# MercurialSDR_FTDI.net
KiCad netlist of a schematic drawn in Altium Designer
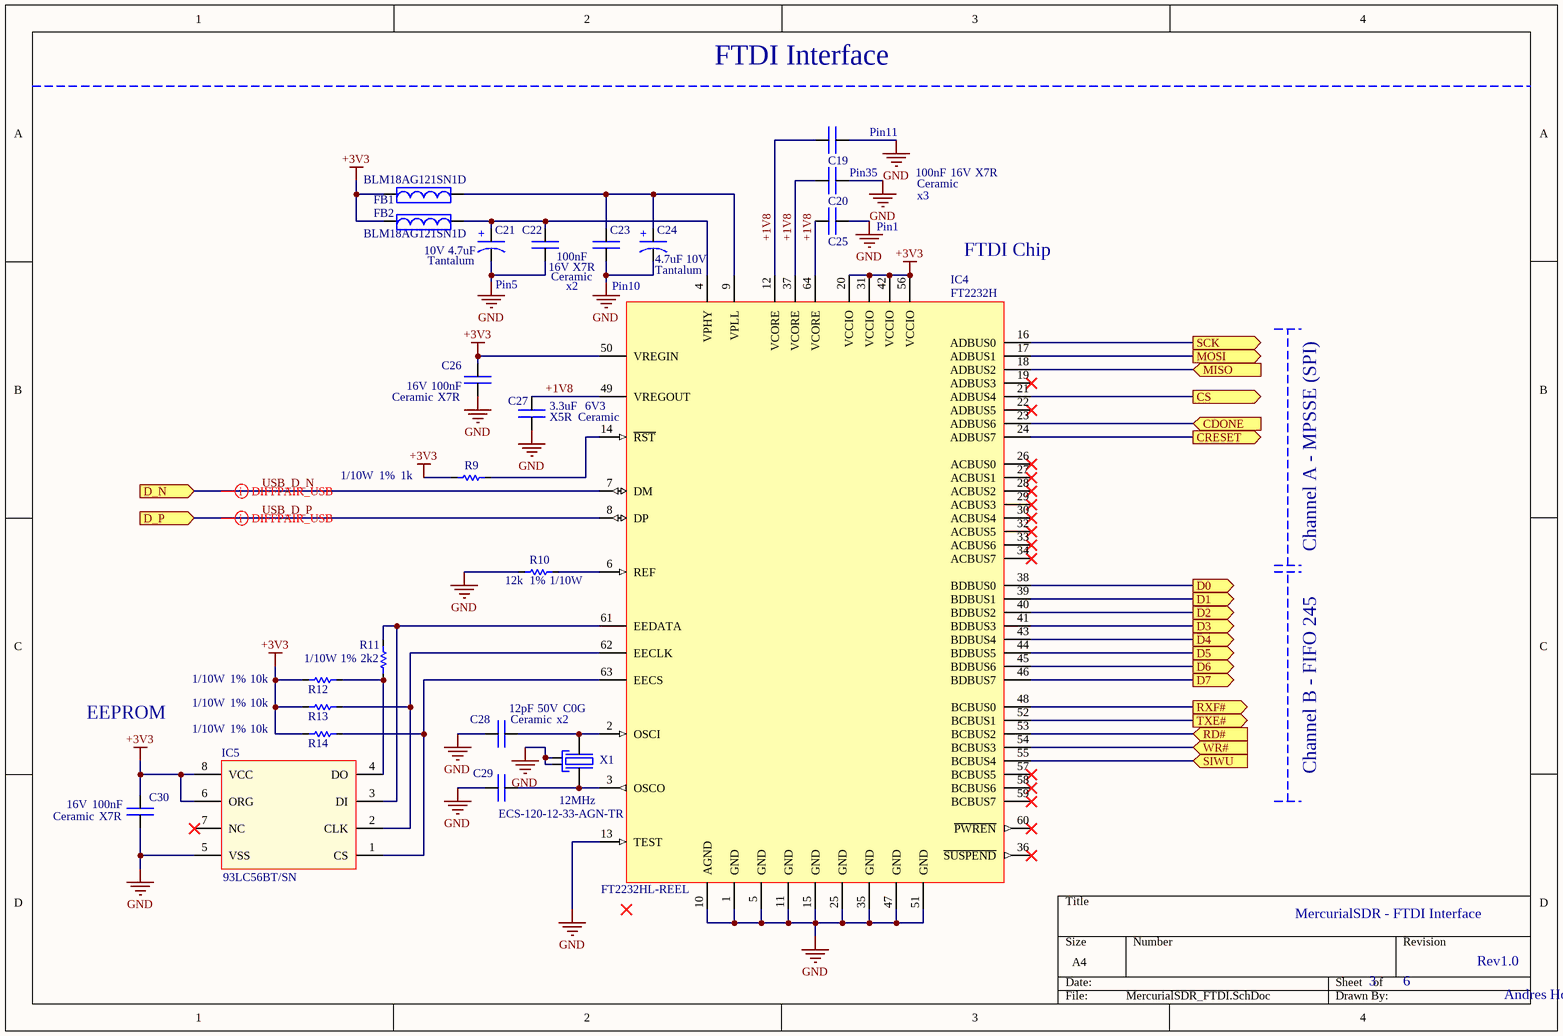
[diagram p0: MercurialSDR_FTDI.SchDoc]

(export (version "E")
  (design (tool "Eeschema 10.0.6"))
  (components
    (comp (ref "C19")
      (value "100nF")
      (footprint "CAP_0603")
      (description "Capacitor no polarizado")
      (fields
        (field (name "TEMP COEF") "X7R")
        (field (name "PART NUMBER") "CL10B104KO8NNNC")
        (field (name "VR") "16V")
        (field (name "MATERIAL") "Ceramic")
        (field (name "Comment") "Capacitor")
      )
      (libsource (lib "MercurialSDR") (part "Cap"))
    )
    (comp (ref "C20")
      (value "Capacitor")
      (footprint "CAP_0603")
      (description "Capacitor no polarizado")
      (fields (field (name "PART NUMBER") "CL10B104KO8NNNC"))
      (libsource (lib "MercurialSDR") (part "Cap"))
    )
    (comp (ref "C21")
      (value "4.7uF")
      (footprint "CAP_TANT_1206")
      (description "Capacitor polarizado")
      (fields
        (field (name "PART NUMBER") "TAJA475K010RNJ")
        (field (name "VR") "10V")
        (field (name "MATERIAL") "Tantalum")
        (field (name "Comment") "Capacitor Polarizado")
      )
      (libsource (lib "MercurialSDR") (part "Cap Pol"))
    )
    (comp (ref "C22")
      (value "100nF")
      (footprint "CAP_0603")
      (description "Capacitor no polarizado")
      (fields
        (field (name "TEMP COEF") "X7R")
        (field (name "PART NUMBER") "CL10B104KO8NNNC")
        (field (name "VR") "16V")
        (field (name "MATERIAL") "Ceramic")
        (field (name "Comment") "Capacitor")
      )
      (libsource (lib "MercurialSDR") (part "Cap"))
    )
    (comp (ref "C23")
      (value "Capacitor")
      (footprint "CAP_0603")
      (description "Capacitor no polarizado")
      (fields (field (name "PART NUMBER") "CL10B104KO8NNNC"))
      (libsource (lib "MercurialSDR") (part "Cap"))
    )
    (comp (ref "C24")
      (value "4.7uF")
      (footprint "CAP_TANT_1206")
      (description "Capacitor polarizado")
      (fields
        (field (name "PART NUMBER") "TAJA475K010RNJ")
        (field (name "VR") "10V")
        (field (name "MATERIAL") "Tantalum")
        (field (name "Comment") "Capacitor Polarizado")
      )
      (libsource (lib "MercurialSDR") (part "Cap Pol"))
    )
    (comp (ref "C25")
      (value "Capacitor")
      (footprint "CAP_0603")
      (description "Capacitor no polarizado")
      (fields (field (name "PART NUMBER") "CL10B104KO8NNNC"))
      (libsource (lib "MercurialSDR") (part "Cap"))
    )
    (comp (ref "C26")
      (value "100nF")
      (footprint "CAP_0603")
      (description "Capacitor no polarizado")
      (fields
        (field (name "TEMP COEF") "X7R")
        (field (name "PART NUMBER") "CL10B104KO8NNNC")
        (field (name "VR") "16V")
        (field (name "MATERIAL") "Ceramic")
        (field (name "Comment") "Capacitor")
      )
      (libsource (lib "MercurialSDR") (part "Cap"))
    )
    (comp (ref "C27")
      (value "3.3uF")
      (footprint "CAP_0603")
      (description "Capacitor no polarizado")
      (fields
        (field (name "TEMP COEF") "X5R")
        (field (name "PART NUMBER") "C0603C335M9PACTU")
        (field (name "VR") "6V3")
        (field (name "MATERIAL") "Ceramic")
        (field (name "Comment") "Capacitor")
      )
      (libsource (lib "MercurialSDR") (part "Cap"))
    )
    (comp (ref "C28")
      (value "12pF")
      (footprint "CAP_0603")
      (description "Capacitor no polarizado")
      (fields
        (field (name "TEMP COEF") "C0G")
        (field (name "PART NUMBER") "CL10C120JB8NNNC")
        (field (name "VR") "50V")
        (field (name "MATERIAL") "Ceramic")
        (field (name "Comment") "Capacitor")
      )
      (libsource (lib "MercurialSDR") (part "Cap"))
    )
    (comp (ref "C29")
      (value "Capacitor")
      (footprint "CAP_0603")
      (description "Capacitor no polarizado")
      (fields (field (name "PART NUMBER") "CL10C120JB8NNNC"))
      (libsource (lib "MercurialSDR") (part "Cap"))
    )
    (comp (ref "C30")
      (value "100nF")
      (footprint "CAP_0603")
      (description "Capacitor no polarizado")
      (fields
        (field (name "TEMP COEF") "X7R")
        (field (name "PART NUMBER") "CL10B104KO8NNNC")
        (field (name "VR") "16V")
        (field (name "MATERIAL") "Ceramic")
        (field (name "Comment") "Capacitor")
      )
      (libsource (lib "MercurialSDR") (part "Cap"))
    )
    (comp (ref "FB1")
      (value "Ferrite Bead")
      (footprint "FERRITE_BEAD_0603")
      (fields (field (name "PART NUMBER") "BLM18AG121SN1D"))
      (libsource (lib "MercurialSDR") (part "Ferrite Bead"))
    )
    (comp (ref "FB2")
      (value "Ferrite Bead")
      (footprint "FERRITE_BEAD_0603")
      (fields (field (name "PART NUMBER") "BLM18AG121SN1D"))
      (libsource (lib "MercurialSDR") (part "Ferrite Bead"))
    )
    (comp (ref "IC4")
      (value "FT2232H")
      (footprint "LQFP_64")
      (description "USB bridge")
      (fields (field (name "PART NUMBER") "FT2232HL-REEL"))
      (libsource (lib "MercurialSDR") (part "FT2232H"))
    )
    (comp (ref "IC5")
      (value "93LC56BT")
      (footprint "SOIC-8")
      (description "EEPROM SPI 2kb (128x16)")
      (fields (field (name "PART NUMBER") "93LC56BT/SN"))
      (libsource (lib "MercurialSDR") (part "93LC56BT/SN"))
    )
    (comp (ref "R9")
      (value "1k")
      (footprint "RES_0603")
      (description "Resistor")
      (fields
        (field (name "POWER") "1/10W")
        (field (name "PART NUMBER") "CR0603-FX-1001ELF")
        (field (name "TOLERANCE") "1%")
        (field (name "Comment") "Resistor SMD")
      )
      (libsource (lib "MercurialSDR") (part "Res"))
    )
    (comp (ref "R10")
      (value "12k")
      (footprint "RES_0603")
      (description "Resistor")
      (fields
        (field (name "POWER") "1/10W")
        (field (name "PART NUMBER") "CR0603-FX-1202ELF")
        (field (name "TOLERANCE") "1%")
        (field (name "Comment") "Resistor SMD")
      )
      (libsource (lib "MercurialSDR") (part "Res"))
    )
    (comp (ref "R11")
      (value "2k2")
      (footprint "RES_0603")
      (description "Resistor")
      (fields
        (field (name "POWER") "1/10W")
        (field (name "PART NUMBER") "CR0603-FX-2201ELF")
        (field (name "TOLERANCE") "1%")
        (field (name "Comment") "Resistor SMD")
      )
      (libsource (lib "MercurialSDR") (part "Res"))
    )
    (comp (ref "R12")
      (value "10k")
      (footprint "RES_0603")
      (description "Resistor")
      (fields
        (field (name "POWER") "1/10W")
        (field (name "PART NUMBER") "CR0603-FX-1002EAS")
        (field (name "TOLERANCE") "1%")
        (field (name "Comment") "Resistor SMD")
      )
      (libsource (lib "MercurialSDR") (part "Res"))
    )
    (comp (ref "R13")
      (value "10k")
      (footprint "RES_0603")
      (description "Resistor")
      (fields
        (field (name "POWER") "1/10W")
        (field (name "PART NUMBER") "CR0603-FX-1002EAS")
        (field (name "TOLERANCE") "1%")
        (field (name "Comment") "Resistor SMD")
      )
      (libsource (lib "MercurialSDR") (part "Res"))
    )
    (comp (ref "R14")
      (value "10k")
      (footprint "RES_0603")
      (description "Resistor")
      (fields
        (field (name "POWER") "1/10W")
        (field (name "PART NUMBER") "CR0603-FX-1002EAS")
        (field (name "TOLERANCE") "1%")
        (field (name "Comment") "Resistor SMD")
      )
      (libsource (lib "MercurialSDR") (part "Res"))
    )
    (comp (ref "X1")
      (value "XTAL_4term")
      (footprint "XTAL_3.2x2.5")
      (description "Oscilador a Cristal")
      (fields (field (name "PART NUMBER") "ECS-120-12-33-AGN-TR") (field (name "FRQUENCY") "12MHz"))
      (libsource (lib "MercurialSDR") (part "XTAL_4term"))
    )
  )
  (nets
    (net (code "1") (name "+3V3") (class "Default")
      (node (ref "C26") (pin "1") (pinfunction "1_1") (pintype "passive"))
      (node (ref "C30") (pin "1") (pinfunction "1_1") (pintype "passive"))
      (node (ref "FB1") (pin "1") (pinfunction "1_1") (pintype "passive"))
      (node (ref "FB2") (pin "1") (pinfunction "1_1") (pintype "passive"))
      (node (ref "IC4") (pin "20") (pinfunction "VCCIO_20") (pintype "power_in"))
      (node (ref "IC4") (pin "31") (pinfunction "VCCIO_31") (pintype "power_in"))
      (node (ref "IC4") (pin "42") (pinfunction "VCCIO_42") (pintype "power_in"))
      (node (ref "IC4") (pin "50") (pinfunction "VREGIN_50") (pintype "power_in"))
      (node (ref "IC4") (pin "56") (pinfunction "VCCIO_56") (pintype "power_in"))
      (node (ref "IC5") (pin "6") (pinfunction "ORG_6") (pintype "passive"))
      (node (ref "IC5") (pin "8") (pinfunction "VCC_8") (pintype "passive"))
      (node (ref "R12") (pin "2") (pinfunction "2_2") (pintype "passive"))
      (node (ref "R13") (pin "1") (pinfunction "1_1") (pintype "passive"))
      (node (ref "R14") (pin "1") (pinfunction "1_1") (pintype "passive"))
      (node (ref "R9") (pin "2") (pinfunction "2_2") (pintype "passive"))
    )
    (net (code "2") (name "/+1V8") (class "Default")
      (node (ref "C19") (pin "1") (pinfunction "1_1") (pintype "passive"))
      (node (ref "C20") (pin "1") (pinfunction "1_1") (pintype "passive"))
      (node (ref "C25") (pin "1") (pinfunction "1_1") (pintype "passive"))
      (node (ref "C27") (pin "1") (pinfunction "1_1") (pintype "passive"))
      (node (ref "IC4") (pin "12") (pinfunction "VCORE_12") (pintype "power_in"))
      (node (ref "IC4") (pin "37") (pinfunction "VCORE_37") (pintype "power_in"))
      (node (ref "IC4") (pin "49") (pinfunction "VREGOUT_49") (pintype "power_in"))
      (node (ref "IC4") (pin "64") (pinfunction "VCORE_64") (pintype "power_in"))
    )
    (net (code "3") (name "/CDONE") (class "Default")
      (node (ref "IC4") (pin "23") (pinfunction "ADBUS6_23") (pintype "passive"))
    )
    (net (code "4") (name "/CRESET") (class "Default")
      (node (ref "IC4") (pin "24") (pinfunction "ADBUS7_24") (pintype "passive"))
    )
    (net (code "5") (name "/CS") (class "Default")
      (node (ref "IC4") (pin "21") (pinfunction "ADBUS4_21") (pintype "passive"))
    )
    (net (code "6") (name "/D0") (class "Default")
      (node (ref "IC4") (pin "38") (pinfunction "BDBUS0_38") (pintype "passive"))
    )
    (net (code "7") (name "/D1") (class "Default")
      (node (ref "IC4") (pin "39") (pinfunction "BDBUS1_39") (pintype "passive"))
    )
    (net (code "8") (name "/D2") (class "Default")
      (node (ref "IC4") (pin "40") (pinfunction "BDBUS2_40") (pintype "passive"))
    )
    (net (code "9") (name "/D3") (class "Default")
      (node (ref "IC4") (pin "41") (pinfunction "BDBUS3_41") (pintype "passive"))
    )
    (net (code "10") (name "/D4") (class "Default")
      (node (ref "IC4") (pin "43") (pinfunction "BDBUS4_43") (pintype "passive"))
    )
    (net (code "11") (name "/D5") (class "Default")
      (node (ref "IC4") (pin "44") (pinfunction "BDBUS5_44") (pintype "passive"))
    )
    (net (code "12") (name "/D6") (class "Default")
      (node (ref "IC4") (pin "45") (pinfunction "BDBUS6_45") (pintype "passive"))
    )
    (net (code "13") (name "/D7") (class "Default")
      (node (ref "IC4") (pin "46") (pinfunction "BDBUS7_46") (pintype "passive"))
    )
    (net (code "14") (name "/MISO") (class "Default")
      (node (ref "IC4") (pin "18") (pinfunction "ADBUS2_18") (pintype "passive"))
    )
    (net (code "15") (name "/MOSI") (class "Default")
      (node (ref "IC4") (pin "17") (pinfunction "ADBUS1_17") (pintype "passive"))
    )
    (net (code "16") (name "/RD#") (class "Default")
      (node (ref "IC4") (pin "53") (pinfunction "BCBUS2_53") (pintype "passive"))
    )
    (net (code "17") (name "/RXF#") (class "Default")
      (node (ref "IC4") (pin "48") (pinfunction "BCBUS0_48") (pintype "passive"))
    )
    (net (code "18") (name "/SCK") (class "Default")
      (node (ref "IC4") (pin "16") (pinfunction "ADBUS0_16") (pintype "passive"))
    )
    (net (code "19") (name "/SIWU") (class "Default")
      (node (ref "IC4") (pin "55") (pinfunction "BCBUS4_55") (pintype "passive"))
    )
    (net (code "20") (name "/TXE#") (class "Default")
      (node (ref "IC4") (pin "52") (pinfunction "BCBUS1_52") (pintype "passive"))
    )
    (net (code "21") (name "/USB_D_N") (class "Default")
      (node (ref "IC4") (pin "7") (pinfunction "DM_7") (pintype "bidirectional"))
    )
    (net (code "22") (name "/USB_D_P") (class "Default")
      (node (ref "IC4") (pin "8") (pinfunction "DP_8") (pintype "bidirectional"))
    )
    (net (code "23") (name "/WR#") (class "Default")
      (node (ref "IC4") (pin "54") (pinfunction "BCBUS3_54") (pintype "passive"))
    )
    (net (code "24") (name "GND") (class "Default")
      (node (ref "C19") (pin "2") (pinfunction "2_2") (pintype "passive"))
      (node (ref "C20") (pin "2") (pinfunction "2_2") (pintype "passive"))
      (node (ref "C21") (pin "2") (pinfunction "2_2") (pintype "passive"))
      (node (ref "C22") (pin "2") (pinfunction "2_2") (pintype "passive"))
      (node (ref "C23") (pin "2") (pinfunction "2_2") (pintype "passive"))
      (node (ref "C24") (pin "2") (pinfunction "2_2") (pintype "passive"))
      (node (ref "C25") (pin "2") (pinfunction "2_2") (pintype "passive"))
      (node (ref "C26") (pin "2") (pinfunction "2_2") (pintype "passive"))
      (node (ref "C27") (pin "2") (pinfunction "2_2") (pintype "passive"))
      (node (ref "C28") (pin "2") (pinfunction "2_2") (pintype "passive"))
      (node (ref "C29") (pin "1") (pinfunction "1_1") (pintype "passive"))
      (node (ref "C30") (pin "2") (pinfunction "2_2") (pintype "passive"))
      (node (ref "IC4") (pin "1") (pinfunction "GND_1") (pintype "power_in"))
      (node (ref "IC4") (pin "10") (pinfunction "AGND_10") (pintype "power_in"))
      (node (ref "IC4") (pin "11") (pinfunction "GND_11") (pintype "power_in"))
      (node (ref "IC4") (pin "13") (pinfunction "TEST_13") (pintype "input"))
      (node (ref "IC4") (pin "15") (pinfunction "GND_15") (pintype "power_in"))
      (node (ref "IC4") (pin "25") (pinfunction "GND_25") (pintype "power_in"))
      (node (ref "IC4") (pin "35") (pinfunction "GND_35") (pintype "power_in"))
      (node (ref "IC4") (pin "47") (pinfunction "GND_47") (pintype "power_in"))
      (node (ref "IC4") (pin "5") (pinfunction "GND_5") (pintype "power_in"))
      (node (ref "IC4") (pin "51") (pinfunction "GND_51") (pintype "power_in"))
      (node (ref "IC5") (pin "5") (pinfunction "VSS_5") (pintype "passive"))
      (node (ref "R10") (pin "2") (pinfunction "2_2") (pintype "passive"))
      (node (ref "X1") (pin "2") (pinfunction "2_2") (pintype "passive"))
      (node (ref "X1") (pin "4") (pinfunction "4_4") (pintype "passive"))
    )
    (net (code "25") (name "Net-(IC4-EECLK)") (class "Default")
      (node (ref "IC4") (pin "62") (pinfunction "EECLK_62") (pintype "passive"))
      (node (ref "IC5") (pin "2") (pinfunction "CLK_2") (pintype "passive"))
      (node (ref "R13") (pin "2") (pinfunction "2_2") (pintype "passive"))
    )
    (net (code "26") (name "Net-(IC4-EECS)") (class "Default")
      (node (ref "IC4") (pin "63") (pinfunction "EECS_63") (pintype "passive"))
      (node (ref "IC5") (pin "1") (pinfunction "CS_1") (pintype "passive"))
      (node (ref "R14") (pin "2") (pinfunction "2_2") (pintype "passive"))
    )
    (net (code "27") (name "Net-(IC4-EEDATA)") (class "Default")
      (node (ref "IC4") (pin "61") (pinfunction "EEDATA_61") (pintype "passive"))
      (node (ref "IC5") (pin "3") (pinfunction "DI_3") (pintype "passive"))
      (node (ref "R11") (pin "2") (pinfunction "2_2") (pintype "passive"))
    )
    (net (code "28") (name "Net-(IC4-OSCI)") (class "Default")
      (node (ref "C28") (pin "1") (pinfunction "1_1") (pintype "passive"))
      (node (ref "IC4") (pin "2") (pinfunction "OSCI_2") (pintype "input"))
      (node (ref "X1") (pin "1") (pinfunction "1_1") (pintype "passive"))
    )
    (net (code "29") (name "Net-(IC4-OSCO)") (class "Default")
      (node (ref "C29") (pin "2") (pinfunction "2_2") (pintype "passive"))
      (node (ref "IC4") (pin "3") (pinfunction "OSCO_3") (pintype "output"))
      (node (ref "X1") (pin "3") (pinfunction "3_3") (pintype "passive"))
    )
    (net (code "30") (name "Net-(IC4-REF)") (class "Default")
      (node (ref "IC4") (pin "6") (pinfunction "REF_6") (pintype "input"))
      (node (ref "R10") (pin "1") (pinfunction "1_1") (pintype "passive"))
    )
    (net (code "31") (name "Net-(IC4-VPHY)") (class "Default")
      (node (ref "C21") (pin "1") (pinfunction "1_1") (pintype "passive"))
      (node (ref "C22") (pin "1") (pinfunction "1_1") (pintype "passive"))
      (node (ref "FB2") (pin "2") (pinfunction "2_2") (pintype "passive"))
      (node (ref "IC4") (pin "4") (pinfunction "VPHY_4") (pintype "power_in"))
    )
    (net (code "32") (name "Net-(IC4-VPLL)") (class "Default")
      (node (ref "C23") (pin "1") (pinfunction "1_1") (pintype "passive"))
      (node (ref "C24") (pin "1") (pinfunction "1_1") (pintype "passive"))
      (node (ref "FB1") (pin "2") (pinfunction "2_2") (pintype "passive"))
      (node (ref "IC4") (pin "9") (pinfunction "VPLL_9") (pintype "power_in"))
    )
    (net (code "33") (name "Net-(IC4-~{RST})") (class "Default")
      (node (ref "IC4") (pin "14") (pinfunction "~{RST}_14") (pintype "input"))
      (node (ref "R9") (pin "1") (pinfunction "1_1") (pintype "passive"))
    )
    (net (code "34") (name "Net-(IC5-DO)") (class "Default")
      (node (ref "IC5") (pin "4") (pinfunction "DO_4") (pintype "passive"))
      (node (ref "R11") (pin "1") (pinfunction "1_1") (pintype "passive"))
      (node (ref "R12") (pin "1") (pinfunction "1_1") (pintype "passive"))
    )
    (net (code "35") (name "unconnected-(IC4-ACBUS0-Pad26)") (class "Default")
      (node (ref "IC4") (pin "26") (pinfunction "ACBUS0_26") (pintype "passive+no_connect"))
    )
    (net (code "36") (name "unconnected-(IC4-ACBUS1-Pad27)") (class "Default")
      (node (ref "IC4") (pin "27") (pinfunction "ACBUS1_27") (pintype "passive+no_connect"))
    )
    (net (code "37") (name "unconnected-(IC4-ACBUS2-Pad28)") (class "Default")
      (node (ref "IC4") (pin "28") (pinfunction "ACBUS2_28") (pintype "passive+no_connect"))
    )
    (net (code "38") (name "unconnected-(IC4-ACBUS3-Pad29)") (class "Default")
      (node (ref "IC4") (pin "29") (pinfunction "ACBUS3_29") (pintype "passive+no_connect"))
    )
    (net (code "39") (name "unconnected-(IC4-ACBUS4-Pad30)") (class "Default")
      (node (ref "IC4") (pin "30") (pinfunction "ACBUS4_30") (pintype "passive+no_connect"))
    )
    (net (code "40") (name "unconnected-(IC4-ACBUS5-Pad32)") (class "Default")
      (node (ref "IC4") (pin "32") (pinfunction "ACBUS5_32") (pintype "passive+no_connect"))
    )
    (net (code "41") (name "unconnected-(IC4-ACBUS6-Pad33)") (class "Default")
      (node (ref "IC4") (pin "33") (pinfunction "ACBUS6_33") (pintype "passive+no_connect"))
    )
    (net (code "42") (name "unconnected-(IC4-ACBUS7-Pad34)") (class "Default")
      (node (ref "IC4") (pin "34") (pinfunction "ACBUS7_34") (pintype "passive+no_connect"))
    )
    (net (code "43") (name "unconnected-(IC4-ADBUS3-Pad19)") (class "Default")
      (node (ref "IC4") (pin "19") (pinfunction "ADBUS3_19") (pintype "passive+no_connect"))
    )
    (net (code "44") (name "unconnected-(IC4-ADBUS5-Pad22)") (class "Default")
      (node (ref "IC4") (pin "22") (pinfunction "ADBUS5_22") (pintype "passive+no_connect"))
    )
    (net (code "45") (name "unconnected-(IC4-BCBUS5-Pad57)") (class "Default")
      (node (ref "IC4") (pin "57") (pinfunction "BCBUS5_57") (pintype "passive+no_connect"))
    )
    (net (code "46") (name "unconnected-(IC4-BCBUS6-Pad58)") (class "Default")
      (node (ref "IC4") (pin "58") (pinfunction "BCBUS6_58") (pintype "passive+no_connect"))
    )
    (net (code "47") (name "unconnected-(IC4-BCBUS7-Pad59)") (class "Default")
      (node (ref "IC4") (pin "59") (pinfunction "BCBUS7_59") (pintype "passive+no_connect"))
    )
    (net (code "48") (name "unconnected-(IC4-~{PWREN}-Pad60)") (class "Default")
      (node (ref "IC4") (pin "60") (pinfunction "~{PWREN}_60") (pintype "output+no_connect"))
    )
    (net (code "49") (name "unconnected-(IC4-~{SUSPEND}-Pad36)") (class "Default")
      (node (ref "IC4") (pin "36") (pinfunction "~{SUSPEND}_36") (pintype "output+no_connect"))
    )
    (net (code "50") (name "unconnected-(IC5-NC-Pad7)") (class "Default")
      (node (ref "IC5") (pin "7") (pinfunction "NC_7") (pintype "passive+no_connect"))
    )
  )
)
